# LightingUPS_v3.net
KiCad netlist of a schematic drawn in EAGLE
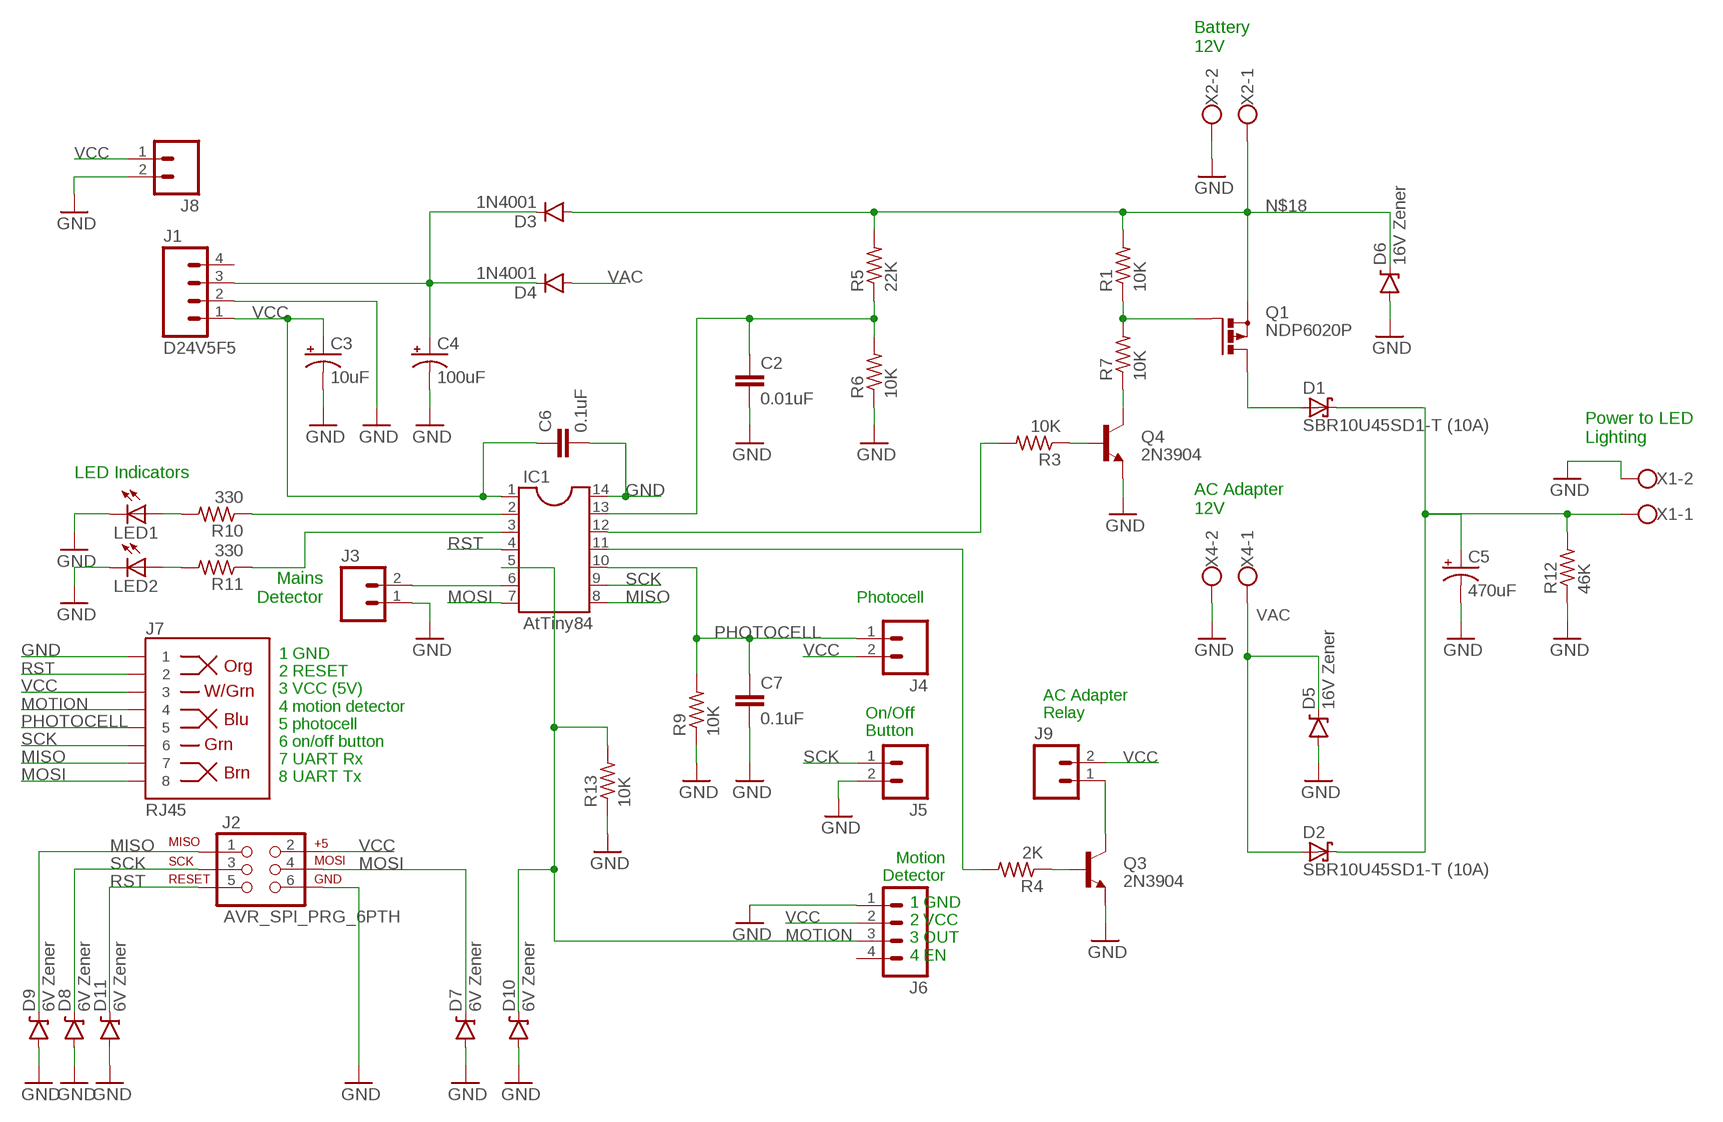
[diagram p0: schematic, sheet 1]

(export (version "E")
  (design (tool "Eeschema 10.0.6"))
  (components
    (comp (ref "C2")
      (value "0.01uF")
      (footprint "eagle-import:CAP-PTH-5MM")
      (libsource (lib "eagle-import") (part "SparkFun-Passives_CAPPTH1"))
    )
    (comp (ref "C3")
      (value "10uF")
      (footprint "eagle-import:CPOL-RADIAL-100UF-25V")
      (libsource (lib "eagle-import") (part "CAP_POLPTH1"))
    )
    (comp (ref "C4")
      (value "100uF")
      (footprint "eagle-import:CPOL-RADIAL-100UF-25V")
      (libsource (lib "eagle-import") (part "CAP_POLPTH1"))
    )
    (comp (ref "C5")
      (value "470uF")
      (footprint "eagle-import:CPOL-RADIAL-1000UF-25V")
      (libsource (lib "eagle-import") (part "CAP_POLPTH4"))
    )
    (comp (ref "C6")
      (value "0.1uF")
      (footprint "eagle-import:CAP-PTH-SMALL")
      (libsource (lib "eagle-import") (part "CAPPTH"))
    )
    (comp (ref "C7")
      (value "0.1uF")
      (footprint "eagle-import:CAP-PTH-SMALL")
      (libsource (lib "eagle-import") (part "CAPPTH"))
    )
    (comp (ref "D1")
      (value "SBR10U45SD1-T (10A)")
      (footprint "eagle-import:DO201T15")
      (libsource (lib "eagle-import") (part "SCHOTTKY-DIODEDO201T15"))
    )
    (comp (ref "D2")
      (value "SBR10U45SD1-T (10A)")
      (footprint "eagle-import:DO201T15")
      (libsource (lib "eagle-import") (part "SCHOTTKY-DIODEDO201T15"))
    )
    (comp (ref "D3")
      (value "1N4001")
      (footprint "eagle-import:DIODE-1N4001")
      (libsource (lib "eagle-import") (part "DIODEPTH"))
    )
    (comp (ref "D4")
      (value "1N4001")
      (footprint "eagle-import:DIODE-1N4001")
      (libsource (lib "eagle-import") (part "DIODEPTH"))
    )
    (comp (ref "D5")
      (value "16V Zener")
      (footprint "eagle-import:DIODE-ZENER")
      (libsource (lib "eagle-import") (part "DIODE-ZENERPTH"))
    )
    (comp (ref "D6")
      (value "16V Zener")
      (footprint "eagle-import:DIODE-ZENER")
      (libsource (lib "eagle-import") (part "DIODE-ZENERPTH"))
    )
    (comp (ref "D7")
      (value "6V Zener")
      (footprint "eagle-import:DIODE-ZENER")
      (libsource (lib "eagle-import") (part "DIODE-ZENERPTH"))
    )
    (comp (ref "D8")
      (value "6V Zener")
      (footprint "eagle-import:DIODE-ZENER")
      (libsource (lib "eagle-import") (part "DIODE-ZENERPTH"))
    )
    (comp (ref "D9")
      (value "6V Zener")
      (footprint "eagle-import:DIODE-ZENER")
      (libsource (lib "eagle-import") (part "DIODE-ZENERPTH"))
    )
    (comp (ref "D10")
      (value "6V Zener")
      (footprint "eagle-import:DIODE-ZENER")
      (libsource (lib "eagle-import") (part "DIODE-ZENERPTH"))
    )
    (comp (ref "D11")
      (value "6V Zener")
      (footprint "eagle-import:DIODE-ZENER")
      (libsource (lib "eagle-import") (part "DIODE-ZENERPTH"))
    )
    (comp (ref "IC1")
      (value "AtTiny84")
      (footprint "eagle-import:DIL14")
      (libsource (lib "eagle-import") (part "DIL14"))
    )
    (comp (ref "J1")
      (value "D24V5F5")
      (footprint "eagle-import:1X04")
      (libsource (lib "eagle-import") (part "M04PTH"))
    )
    (comp (ref "J2")
      (value "AVR_SPI_PRG_6PTH")
      (footprint "eagle-import:2X3")
      (libsource (lib "eagle-import") (part "AVR_SPI_PRG_6PTH"))
    )
    (comp (ref "J3")
      (value "M02PTH")
      (footprint "eagle-import:1X02")
      (libsource (lib "eagle-import") (part "M02PTH"))
    )
    (comp (ref "J4")
      (value "M02PTH")
      (footprint "eagle-import:1X02")
      (libsource (lib "eagle-import") (part "M02PTH"))
    )
    (comp (ref "J5")
      (value "M02PTH")
      (footprint "eagle-import:1X02")
      (libsource (lib "eagle-import") (part "M02PTH"))
    )
    (comp (ref "J6")
      (value "M04PTH")
      (footprint "eagle-import:1X04")
      (libsource (lib "eagle-import") (part "M04PTH"))
    )
    (comp (ref "J7")
      (value "RJ45")
      (footprint "eagle-import:RJ45-8")
      (libsource (lib "eagle-import") (part "RJ45-8PTH"))
    )
    (comp (ref "J8")
      (value "M02PTH")
      (footprint "eagle-import:1X02")
      (libsource (lib "eagle-import") (part "M02PTH"))
    )
    (comp (ref "J9")
      (value "M02PTH")
      (footprint "eagle-import:1X02")
      (libsource (lib "eagle-import") (part "M02PTH"))
    )
    (comp (ref "LED1")
      (value "LED5MM")
      (footprint "eagle-import:LED5MM")
      (libsource (lib "eagle-import") (part "LED5MM"))
    )
    (comp (ref "LED2")
      (value "LED5MM")
      (footprint "eagle-import:LED5MM")
      (libsource (lib "eagle-import") (part "LED5MM"))
    )
    (comp (ref "Q1")
      (value "NDP6020P")
      (footprint "eagle-import:TO220BV")
      (libsource (lib "eagle-import") (part "PMOSFET_PTO220BV"))
    )
    (comp (ref "Q3")
      (value "2N3904")
      (footprint "eagle-import:TO-92-AMMO")
      (libsource (lib "eagle-import") (part "TRANSISTOR_NPNTO-92-AMMO"))
    )
    (comp (ref "Q4")
      (value "2N3904")
      (footprint "eagle-import:TO-92-AMMO")
      (libsource (lib "eagle-import") (part "TRANSISTOR_NPNTO-92-AMMO"))
    )
    (comp (ref "R1")
      (value "10K")
      (footprint "eagle-import:0204_5")
      (libsource (lib "eagle-import") (part "R-US_0204/5"))
    )
    (comp (ref "R3")
      (value "10K")
      (footprint "eagle-import:0204_5")
      (libsource (lib "eagle-import") (part "R-US_0204/5"))
    )
    (comp (ref "R4")
      (value "2K")
      (footprint "eagle-import:0204_5")
      (libsource (lib "eagle-import") (part "R-US_0204/5"))
    )
    (comp (ref "R5")
      (value "22K")
      (footprint "eagle-import:0204_5")
      (libsource (lib "eagle-import") (part "R-US_0204/5"))
    )
    (comp (ref "R6")
      (value "10K")
      (footprint "eagle-import:0204_5")
      (libsource (lib "eagle-import") (part "R-US_0204/5"))
    )
    (comp (ref "R7")
      (value "10K")
      (footprint "eagle-import:0204_5")
      (libsource (lib "eagle-import") (part "R-US_0204/5"))
    )
    (comp (ref "R9")
      (value "10K")
      (footprint "eagle-import:0204_5")
      (libsource (lib "eagle-import") (part "R-US_0204/5"))
    )
    (comp (ref "R10")
      (value "330")
      (footprint "eagle-import:0204_5")
      (libsource (lib "eagle-import") (part "R-US_0204/5"))
    )
    (comp (ref "R11")
      (value "330")
      (footprint "eagle-import:0204_5")
      (libsource (lib "eagle-import") (part "R-US_0204/5"))
    )
    (comp (ref "R12")
      (value "46K")
      (footprint "eagle-import:0204_5")
      (libsource (lib "eagle-import") (part "R-US_0204/5"))
    )
    (comp (ref "R13")
      (value "10K")
      (footprint "eagle-import:0204_5")
      (libsource (lib "eagle-import") (part "R-US_0204/5"))
    )
    (comp (ref "X1")
      (value "W237-102")
      (footprint "eagle-import:W237-102")
      (fields (field (name "MPN") "237-102"))
      (libsource (lib "eagle-import") (part "W237-102"))
    )
    (comp (ref "X2")
      (value "W237-102")
      (footprint "eagle-import:W237-102")
      (fields (field (name "MPN") "237-102"))
      (libsource (lib "eagle-import") (part "W237-102"))
    )
    (comp (ref "X4")
      (value "W237-102")
      (footprint "eagle-import:W237-102")
      (fields (field (name "MPN") "237-102"))
      (libsource (lib "eagle-import") (part "W237-102"))
    )
  )
  (nets
    (net (code "1") (name "/MISO") (class "Default")
      (node (ref "D9") (pin "P$1") (pinfunction "C_P$1") (pintype "passive"))
      (node (ref "IC1") (pin "8") (pinfunction "8_8") (pintype "passive"))
      (node (ref "J2") (pin "1") (pinfunction "1_1") (pintype "passive"))
      (node (ref "J7") (pin "7") (pinfunction "7_7") (pintype "bidirectional"))
    )
    (net (code "2") (name "/MOSI") (class "Default")
      (node (ref "D7") (pin "P$1") (pinfunction "C_P$1") (pintype "passive"))
      (node (ref "IC1") (pin "7") (pinfunction "7_7") (pintype "passive"))
      (node (ref "J2") (pin "4") (pinfunction "4_4") (pintype "passive"))
      (node (ref "J7") (pin "8") (pinfunction "8_8") (pintype "bidirectional"))
    )
    (net (code "3") (name "/MOTION") (class "Default")
      (node (ref "D10") (pin "P$1") (pinfunction "C_P$1") (pintype "passive"))
      (node (ref "IC1") (pin "5") (pinfunction "5_5") (pintype "passive"))
      (node (ref "J6") (pin "3") (pinfunction "3_3") (pintype "passive"))
      (node (ref "J7") (pin "4") (pinfunction "4_4") (pintype "bidirectional"))
      (node (ref "R13") (pin "2") (pinfunction "2_2") (pintype "passive"))
    )
    (net (code "4") (name "/N$18") (class "Default")
      (node (ref "D3") (pin "A") (pinfunction "A_A") (pintype "passive"))
      (node (ref "D6") (pin "P$1") (pinfunction "C_P$1") (pintype "passive"))
      (node (ref "Q1") (pin "S") (pinfunction "S_S") (pintype "passive"))
      (node (ref "R1") (pin "2") (pinfunction "2_2") (pintype "passive"))
      (node (ref "R5") (pin "2") (pinfunction "2_2") (pintype "passive"))
      (node (ref "X2") (pin "1") (pinfunction "KL_1") (pintype "passive"))
    )
    (net (code "5") (name "/PHOTOCELL") (class "Default")
      (node (ref "C7") (pin "1") (pinfunction "1_1") (pintype "passive"))
      (node (ref "IC1") (pin "10") (pinfunction "10_10") (pintype "passive"))
      (node (ref "J4") (pin "1") (pinfunction "1_1") (pintype "passive"))
      (node (ref "J7") (pin "5") (pinfunction "5_5") (pintype "bidirectional"))
      (node (ref "R9") (pin "2") (pinfunction "2_2") (pintype "passive"))
    )
    (net (code "6") (name "/RST") (class "Default")
      (node (ref "D11") (pin "P$1") (pinfunction "C_P$1") (pintype "passive"))
      (node (ref "IC1") (pin "4") (pinfunction "4_4") (pintype "passive"))
      (node (ref "J2") (pin "5") (pinfunction "5_5") (pintype "passive"))
      (node (ref "J7") (pin "2") (pinfunction "2_2") (pintype "bidirectional"))
    )
    (net (code "7") (name "/SCK") (class "Default")
      (node (ref "D8") (pin "P$1") (pinfunction "C_P$1") (pintype "passive"))
      (node (ref "IC1") (pin "9") (pinfunction "9_9") (pintype "passive"))
      (node (ref "J2") (pin "3") (pinfunction "3_3") (pintype "passive"))
      (node (ref "J5") (pin "1") (pinfunction "1_1") (pintype "passive"))
      (node (ref "J7") (pin "6") (pinfunction "6_6") (pintype "bidirectional"))
    )
    (net (code "8") (name "/VAC") (class "Default")
      (node (ref "D2") (pin "A") (pinfunction "A_A") (pintype "passive"))
      (node (ref "D4") (pin "A") (pinfunction "A_A") (pintype "passive"))
      (node (ref "D5") (pin "P$1") (pinfunction "C_P$1") (pintype "passive"))
      (node (ref "X4") (pin "1") (pinfunction "KL_1") (pintype "passive"))
    )
    (net (code "9") (name "/VCC") (class "Default")
      (node (ref "C3") (pin "1") (pinfunction "+_1") (pintype "passive"))
      (node (ref "C6") (pin "1") (pinfunction "1_1") (pintype "passive"))
      (node (ref "IC1") (pin "1") (pinfunction "1_1") (pintype "passive"))
      (node (ref "J1") (pin "1") (pinfunction "1_1") (pintype "passive"))
      (node (ref "J2") (pin "2") (pinfunction "2_2") (pintype "passive"))
      (node (ref "J4") (pin "2") (pinfunction "2_2") (pintype "passive"))
      (node (ref "J6") (pin "2") (pinfunction "2_2") (pintype "passive"))
      (node (ref "J7") (pin "3") (pinfunction "3_3") (pintype "bidirectional"))
      (node (ref "J8") (pin "1") (pinfunction "1_1") (pintype "passive"))
      (node (ref "J9") (pin "2") (pinfunction "2_2") (pintype "passive"))
    )
    (net (code "10") (name "GND") (class "Default")
      (node (ref "C2") (pin "2") (pinfunction "2_2") (pintype "passive"))
      (node (ref "C3") (pin "2") (pinfunction "-_2") (pintype "passive"))
      (node (ref "C4") (pin "2") (pinfunction "-_2") (pintype "passive"))
      (node (ref "C5") (pin "-") (pinfunction "-_-") (pintype "passive"))
      (node (ref "C6") (pin "2") (pinfunction "2_2") (pintype "passive"))
      (node (ref "C7") (pin "2") (pinfunction "2_2") (pintype "passive"))
      (node (ref "D10") (pin "P$2") (pinfunction "A_P$2") (pintype "passive"))
      (node (ref "D11") (pin "P$2") (pinfunction "A_P$2") (pintype "passive"))
      (node (ref "D5") (pin "P$2") (pinfunction "A_P$2") (pintype "passive"))
      (node (ref "D6") (pin "P$2") (pinfunction "A_P$2") (pintype "passive"))
      (node (ref "D7") (pin "P$2") (pinfunction "A_P$2") (pintype "passive"))
      (node (ref "D8") (pin "P$2") (pinfunction "A_P$2") (pintype "passive"))
      (node (ref "D9") (pin "P$2") (pinfunction "A_P$2") (pintype "passive"))
      (node (ref "IC1") (pin "14") (pinfunction "14_14") (pintype "passive"))
      (node (ref "J1") (pin "2") (pinfunction "2_2") (pintype "passive"))
      (node (ref "J2") (pin "6") (pinfunction "6_6") (pintype "passive"))
      (node (ref "J3") (pin "1") (pinfunction "1_1") (pintype "passive"))
      (node (ref "J5") (pin "2") (pinfunction "2_2") (pintype "passive"))
      (node (ref "J6") (pin "1") (pinfunction "1_1") (pintype "passive"))
      (node (ref "J7") (pin "1") (pinfunction "1_1") (pintype "bidirectional"))
      (node (ref "J8") (pin "2") (pinfunction "2_2") (pintype "passive"))
      (node (ref "LED1") (pin "K") (pinfunction "C_K") (pintype "passive"))
      (node (ref "LED2") (pin "K") (pinfunction "C_K") (pintype "passive"))
      (node (ref "Q3") (pin "1") (pinfunction "E_1") (pintype "passive"))
      (node (ref "Q4") (pin "1") (pinfunction "E_1") (pintype "passive"))
      (node (ref "R12") (pin "1") (pinfunction "1_1") (pintype "passive"))
      (node (ref "R13") (pin "1") (pinfunction "1_1") (pintype "passive"))
      (node (ref "R6") (pin "1") (pinfunction "1_1") (pintype "passive"))
      (node (ref "R9") (pin "1") (pinfunction "1_1") (pintype "passive"))
      (node (ref "X1") (pin "2") (pinfunction "KL_2") (pintype "passive"))
      (node (ref "X2") (pin "2") (pinfunction "KL_2") (pintype "passive"))
      (node (ref "X4") (pin "2") (pinfunction "KL_2") (pintype "passive"))
    )
    (net (code "11") (name "Net-(C2-Pad1)") (class "Default")
      (node (ref "C2") (pin "1") (pinfunction "1_1") (pintype "passive"))
      (node (ref "IC1") (pin "13") (pinfunction "13_13") (pintype "passive"))
      (node (ref "R5") (pin "1") (pinfunction "1_1") (pintype "passive"))
      (node (ref "R6") (pin "2") (pinfunction "2_2") (pintype "passive"))
    )
    (net (code "12") (name "Net-(C4-+)") (class "Default")
      (node (ref "C4") (pin "1") (pinfunction "+_1") (pintype "passive"))
      (node (ref "D3") (pin "C") (pinfunction "C_C") (pintype "passive"))
      (node (ref "D4") (pin "C") (pinfunction "C_C") (pintype "passive"))
      (node (ref "J1") (pin "3") (pinfunction "3_3") (pintype "passive"))
    )
    (net (code "13") (name "Net-(D1-PadA)") (class "Default")
      (node (ref "D1") (pin "A") (pinfunction "A_A") (pintype "passive"))
      (node (ref "Q1") (pin "D") (pinfunction "D_D") (pintype "passive"))
    )
    (net (code "14") (name "Net-(IC1-Pad2)") (class "Default")
      (node (ref "IC1") (pin "2") (pinfunction "2_2") (pintype "passive"))
      (node (ref "R10") (pin "1") (pinfunction "1_1") (pintype "passive"))
    )
    (net (code "15") (name "Net-(IC1-Pad3)") (class "Default")
      (node (ref "IC1") (pin "3") (pinfunction "3_3") (pintype "passive"))
      (node (ref "R11") (pin "1") (pinfunction "1_1") (pintype "passive"))
    )
    (net (code "16") (name "Net-(IC1-Pad6)") (class "Default")
      (node (ref "IC1") (pin "6") (pinfunction "6_6") (pintype "passive"))
      (node (ref "J3") (pin "2") (pinfunction "2_2") (pintype "passive"))
    )
    (net (code "17") (name "Net-(IC1-Pad11)") (class "Default")
      (node (ref "IC1") (pin "11") (pinfunction "11_11") (pintype "passive"))
      (node (ref "R4") (pin "2") (pinfunction "2_2") (pintype "passive"))
    )
    (net (code "18") (name "Net-(IC1-Pad12)") (class "Default")
      (node (ref "IC1") (pin "12") (pinfunction "12_12") (pintype "passive"))
      (node (ref "R3") (pin "2") (pinfunction "2_2") (pintype "passive"))
    )
    (net (code "19") (name "Net-(LED1-PadA)") (class "Default")
      (node (ref "LED1") (pin "A") (pinfunction "A_A") (pintype "passive"))
      (node (ref "R10") (pin "2") (pinfunction "2_2") (pintype "passive"))
    )
    (net (code "20") (name "Net-(LED2-PadA)") (class "Default")
      (node (ref "LED2") (pin "A") (pinfunction "A_A") (pintype "passive"))
      (node (ref "R11") (pin "2") (pinfunction "2_2") (pintype "passive"))
    )
    (net (code "21") (name "Net-(Q1-PadG)") (class "Default")
      (node (ref "Q1") (pin "G") (pinfunction "G_G") (pintype "passive"))
      (node (ref "R1") (pin "1") (pinfunction "1_1") (pintype "passive"))
      (node (ref "R7") (pin "2") (pinfunction "2_2") (pintype "passive"))
    )
    (net (code "22") (name "Net-(Q3-B)") (class "Default")
      (node (ref "Q3") (pin "2") (pinfunction "B_2") (pintype "passive"))
      (node (ref "R4") (pin "1") (pinfunction "1_1") (pintype "passive"))
    )
    (net (code "23") (name "Net-(Q3-C)") (class "Default")
      (node (ref "J9") (pin "1") (pinfunction "1_1") (pintype "passive"))
      (node (ref "Q3") (pin "3") (pinfunction "C_3") (pintype "passive"))
    )
    (net (code "24") (name "Net-(Q4-B)") (class "Default")
      (node (ref "Q4") (pin "2") (pinfunction "B_2") (pintype "passive"))
      (node (ref "R3") (pin "1") (pinfunction "1_1") (pintype "passive"))
    )
    (net (code "25") (name "Net-(Q4-C)") (class "Default")
      (node (ref "Q4") (pin "3") (pinfunction "C_3") (pintype "passive"))
      (node (ref "R7") (pin "1") (pinfunction "1_1") (pintype "passive"))
    )
    (net (code "26") (name "Net-(X1A-KL)") (class "Default")
      (node (ref "C5") (pin "+") (pinfunction "+_+") (pintype "passive"))
      (node (ref "D1") (pin "C") (pinfunction "C_C") (pintype "passive"))
      (node (ref "D2") (pin "C") (pinfunction "C_C") (pintype "passive"))
      (node (ref "R12") (pin "2") (pinfunction "2_2") (pintype "passive"))
      (node (ref "X1") (pin "1") (pinfunction "KL_1") (pintype "passive"))
    )
    (net (code "27") (name "unconnected-(J1-Pad4)") (class "Default")
      (node (ref "J1") (pin "4") (pinfunction "4_4") (pintype "passive"))
    )
    (net (code "28") (name "unconnected-(J6-Pad4)") (class "Default")
      (node (ref "J6") (pin "4") (pinfunction "4_4") (pintype "passive"))
    )
  )
)
